# mp3.net
KiCad netlist of a schematic drawn in EAGLE
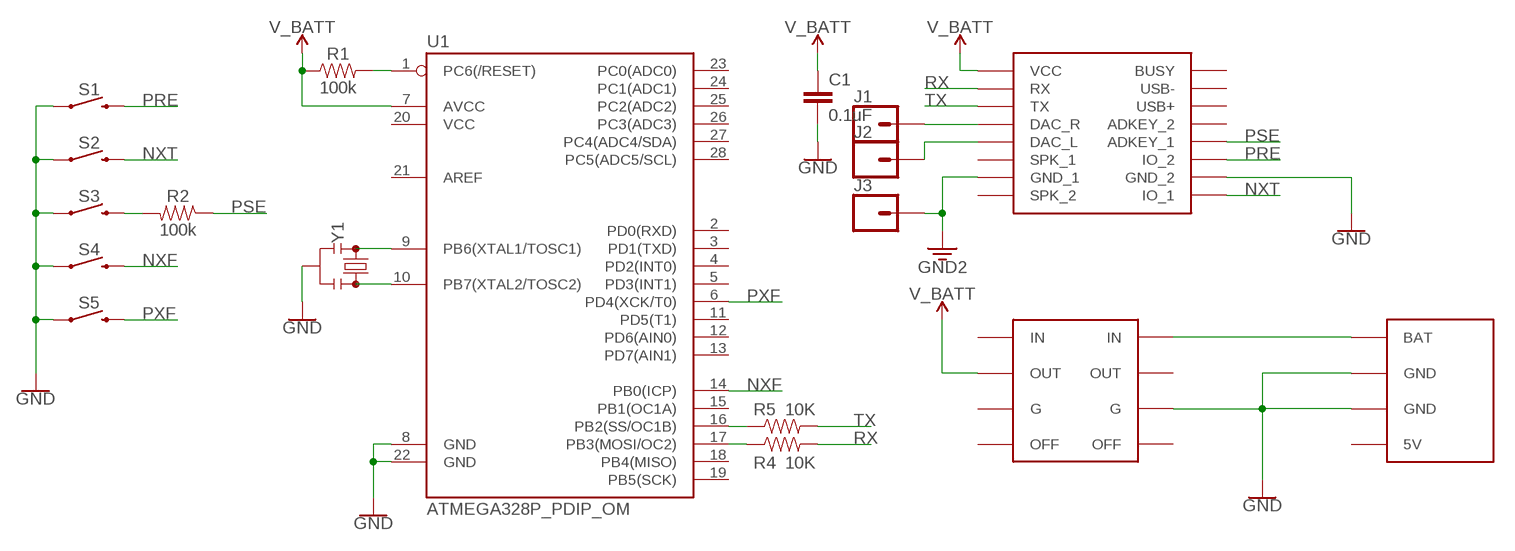
[diagram p0: schematic, sheet 1]

(export (version "E")
  (design (tool "Eeschema 10.0.6"))
  (components
    (comp (ref "C1")
      (value "0.1uF")
      (footprint "eagle-import:CAP-PTH-SMALL-KIT")
      (libsource (lib "eagle-import") (part "0.1UF-KIT-EZ-50V-20%"))
    )
    (comp (ref "J1")
      (value "CONN_01PTH_NO_SILK_KIT")
      (footprint "eagle-import:1X01NS_KIT")
      (libsource (lib "eagle-import") (part "CONN_01PTH_NO_SILK_KIT"))
    )
    (comp (ref "J2")
      (value "CONN_01PTH_NO_SILK_KIT")
      (footprint "eagle-import:1X01NS_KIT")
      (libsource (lib "eagle-import") (part "CONN_01PTH_NO_SILK_KIT"))
    )
    (comp (ref "J3")
      (value "CONN_01PTH_NO_SILK_KIT")
      (footprint "eagle-import:1X01NS_KIT")
      (libsource (lib "eagle-import") (part "CONN_01PTH_NO_SILK_KIT"))
    )
    (comp (ref "R1")
      (value "100k")
      (footprint "eagle-import:AXIAL-0.3")
      (libsource (lib "eagle-import") (part "100KOHM-HORIZ-1/4W-1%"))
    )
    (comp (ref "R2")
      (value "100k")
      (footprint "eagle-import:AXIAL-0.3")
      (libsource (lib "eagle-import") (part "100KOHM-HORIZ-1/4W-1%"))
    )
    (comp (ref "R4")
      (value "10K")
      (footprint "eagle-import:AXIAL-0.3")
      (libsource (lib "eagle-import") (part "100KOHM-HORIZ-1/4W-1%"))
    )
    (comp (ref "R5")
      (value "10K")
      (footprint "eagle-import:AXIAL-0.3")
      (libsource (lib "eagle-import") (part "100KOHM-HORIZ-1/4W-1%"))
    )
    (comp (ref "S1")
      (value "MOMENTARY-SWITCH-SPST-PTH-RIGHT-ANGLE")
      (footprint "eagle-import:TACTILE_SWITCH_PTH_RIGHT_ANGLE")
      (libsource (lib "eagle-import") (part "MOMENTARY-SWITCH-SPST-PTH-RIGHT-ANGLE"))
    )
    (comp (ref "S2")
      (value "MOMENTARY-SWITCH-SPST-PTH-RIGHT-ANGLE")
      (footprint "eagle-import:TACTILE_SWITCH_PTH_RIGHT_ANGLE")
      (libsource (lib "eagle-import") (part "MOMENTARY-SWITCH-SPST-PTH-RIGHT-ANGLE"))
    )
    (comp (ref "S3")
      (value "MOMENTARY-SWITCH-SPST-PTH-RIGHT-ANGLE")
      (footprint "eagle-import:TACTILE_SWITCH_PTH_RIGHT_ANGLE")
      (libsource (lib "eagle-import") (part "MOMENTARY-SWITCH-SPST-PTH-RIGHT-ANGLE"))
    )
    (comp (ref "S4")
      (value "MOMENTARY-SWITCH-SPST-PTH-RIGHT-ANGLE")
      (footprint "eagle-import:TACTILE_SWITCH_PTH_RIGHT_ANGLE")
      (libsource (lib "eagle-import") (part "MOMENTARY-SWITCH-SPST-PTH-RIGHT-ANGLE"))
    )
    (comp (ref "S5")
      (value "MOMENTARY-SWITCH-SPST-PTH-RIGHT-ANGLE")
      (footprint "eagle-import:TACTILE_SWITCH_PTH_RIGHT_ANGLE")
      (libsource (lib "eagle-import") (part "MOMENTARY-SWITCH-SPST-PTH-RIGHT-ANGLE"))
    )
    (comp (ref "U$1")
      (value "DFPLAYER")
      (footprint "eagle-import:DFPLAYER")
      (libsource (lib "eagle-import") (part "DFPLAYER"))
    )
    (comp (ref "U$2")
      (value "ADAFRUIT_SOFTPOWER")
      (footprint "eagle-import:ADAFRUIT_SOFTPOWER")
      (libsource (lib "eagle-import") (part "ADAFRUIT_SOFTPOWER"))
    )
    (comp (ref "U$3")
      (value "ADAFRUIT_CHARGER")
      (footprint "eagle-import:ADAFRUIT_CHARGER")
      (libsource (lib "eagle-import") (part "ADAFRUIT_CHARGER"))
    )
    (comp (ref "U1")
      (value "ATMEGA328P_PDIP_OM")
      (footprint "eagle-import:DIP28_OMILL")
      (libsource (lib "eagle-import") (part "ATMEGA328P_PDIP_OM"))
    )
    (comp (ref "Y1")
      (value "RESONATOROM")
      (footprint "eagle-import:RESONATOR-PTH-7.6X3.3-OM")
      (libsource (lib "eagle-import") (part "RESONATOROM"))
    )
  )
  (nets
    (net (code "1") (name "/NXF") (class "Default")
      (node (ref "S4") (pin "2") (pinfunction "2_2") (pintype "passive"))
      (node (ref "U1") (pin "14") (pinfunction "PB0(ICP)_14") (pintype "bidirectional"))
    )
    (net (code "2") (name "/NXT") (class "Default")
      (node (ref "S2") (pin "2") (pinfunction "2_2") (pintype "passive"))
      (node (ref "U$1") (pin "IO1") (pinfunction "IO_1_IO1") (pintype "bidirectional"))
    )
    (net (code "3") (name "/PRE") (class "Default")
      (node (ref "S1") (pin "2") (pinfunction "2_2") (pintype "passive"))
      (node (ref "U$1") (pin "IO2") (pinfunction "IO_2_IO2") (pintype "bidirectional"))
    )
    (net (code "4") (name "/PSE") (class "Default")
      (node (ref "R2") (pin "P$1") (pinfunction "1_P$1") (pintype "passive"))
      (node (ref "U$1") (pin "ADKEY1") (pinfunction "ADKEY_1_ADKEY1") (pintype "bidirectional"))
    )
    (net (code "5") (name "/PXF") (class "Default")
      (node (ref "S5") (pin "2") (pinfunction "2_2") (pintype "passive"))
      (node (ref "U1") (pin "6") (pinfunction "PD4(XCK/T0)_6") (pintype "bidirectional"))
    )
    (net (code "6") (name "/RX") (class "Default")
      (node (ref "R5") (pin "P$2") (pinfunction "2_P$2") (pintype "passive"))
      (node (ref "U$1") (pin "RX") (pinfunction "RX_RX") (pintype "bidirectional"))
    )
    (net (code "7") (name "/TX") (class "Default")
      (node (ref "R4") (pin "P$2") (pinfunction "2_P$2") (pintype "passive"))
      (node (ref "U$1") (pin "TX") (pinfunction "TX_TX") (pintype "bidirectional"))
    )
    (net (code "8") (name "GND") (class "Default")
      (node (ref "C1") (pin "2") (pinfunction "2_2") (pintype "passive"))
      (node (ref "S1") (pin "1") (pinfunction "1_1") (pintype "passive"))
      (node (ref "S2") (pin "1") (pinfunction "1_1") (pintype "passive"))
      (node (ref "S3") (pin "1") (pinfunction "1_1") (pintype "passive"))
      (node (ref "S4") (pin "1") (pinfunction "1_1") (pintype "passive"))
      (node (ref "S5") (pin "1") (pinfunction "1_1") (pintype "passive"))
      (node (ref "U$1") (pin "GND_2") (pinfunction "GND_2_GND_2") (pintype "bidirectional"))
      (node (ref "U$2") (pin "P$2") (pinfunction "G_P$2") (pintype "bidirectional"))
      (node (ref "U$3") (pin "P$2") (pinfunction "GND_P$2") (pintype "bidirectional"))
      (node (ref "U$3") (pin "P$3") (pinfunction "GND_P$3") (pintype "bidirectional"))
      (node (ref "U1") (pin "22") (pinfunction "GND_22") (pintype "bidirectional"))
      (node (ref "U1") (pin "8") (pinfunction "GND_8") (pintype "bidirectional"))
      (node (ref "Y1") (pin "2") (pinfunction "2_2") (pintype "passive"))
    )
    (net (code "9") (name "GND2") (class "Default")
      (node (ref "J3") (pin "1") (pinfunction "1_1") (pintype "passive"))
      (node (ref "U$1") (pin "GND_1") (pinfunction "GND_1_GND_1") (pintype "bidirectional"))
    )
    (net (code "10") (name "Net-(J1-Pad1)") (class "Default")
      (node (ref "J1") (pin "1") (pinfunction "1_1") (pintype "passive"))
      (node (ref "U$1") (pin "DAC_R") (pinfunction "DAC_R_DAC_R") (pintype "bidirectional"))
    )
    (net (code "11") (name "Net-(J2-Pad1)") (class "Default")
      (node (ref "J2") (pin "1") (pinfunction "1_1") (pintype "passive"))
      (node (ref "U$1") (pin "DAC_L") (pinfunction "DAC_L_DAC_L") (pintype "bidirectional"))
    )
    (net (code "12") (name "Net-(R1-2)") (class "Default")
      (node (ref "R1") (pin "P$2") (pinfunction "2_P$2") (pintype "passive"))
      (node (ref "U1") (pin "1") (pinfunction "PC6(/RESET)_1") (pintype "bidirectional"))
    )
    (net (code "13") (name "Net-(R2-2)") (class "Default")
      (node (ref "R2") (pin "P$2") (pinfunction "2_P$2") (pintype "passive"))
      (node (ref "S3") (pin "2") (pinfunction "2_2") (pintype "passive"))
    )
    (net (code "14") (name "Net-(R4-1)") (class "Default")
      (node (ref "R4") (pin "P$1") (pinfunction "1_P$1") (pintype "passive"))
      (node (ref "U1") (pin "16") (pinfunction "PB2(SS/OC1B)_16") (pintype "bidirectional"))
    )
    (net (code "15") (name "Net-(R5-1)") (class "Default")
      (node (ref "R5") (pin "P$1") (pinfunction "1_P$1") (pintype "passive"))
      (node (ref "U1") (pin "17") (pinfunction "PB3(MOSI/OC2)_17") (pintype "bidirectional"))
    )
    (net (code "16") (name "Net-(U$3-BAT)") (class "Default")
      (node (ref "U$2") (pin "P$4") (pinfunction "IN_P$4") (pintype "bidirectional"))
      (node (ref "U$3") (pin "P$1") (pinfunction "BAT_P$1") (pintype "bidirectional"))
    )
    (net (code "17") (name "Net-(U1-PB6(XTAL1{slash}TOSC1))") (class "Default")
      (node (ref "U1") (pin "9") (pinfunction "PB6(XTAL1/TOSC1)_9") (pintype "bidirectional"))
      (node (ref "Y1") (pin "1") (pinfunction "1_1") (pintype "passive"))
    )
    (net (code "18") (name "Net-(U1-PB7(XTAL2{slash}TOSC2))") (class "Default")
      (node (ref "U1") (pin "10") (pinfunction "PB7(XTAL2/TOSC2)_10") (pintype "bidirectional"))
      (node (ref "Y1") (pin "3") (pinfunction "3_3") (pintype "passive"))
    )
    (net (code "19") (name "V_BATT") (class "Default")
      (node (ref "C1") (pin "1") (pinfunction "1_1") (pintype "passive"))
      (node (ref "R1") (pin "P$1") (pinfunction "1_P$1") (pintype "passive"))
      (node (ref "U$1") (pin "VCC") (pinfunction "VCC_VCC") (pintype "bidirectional"))
      (node (ref "U$2") (pin "P$6") (pinfunction "OUT_P$6") (pintype "bidirectional"))
      (node (ref "U1") (pin "7") (pinfunction "AVCC_7") (pintype "bidirectional"))
    )
    (net (code "20") (name "unconnected-(U$1-ADKEY_2-PadADKEY2)") (class "Default")
      (node (ref "U$1") (pin "ADKEY2") (pinfunction "ADKEY_2_ADKEY2") (pintype "bidirectional"))
    )
    (net (code "21") (name "unconnected-(U$1-PadBUSY)") (class "Default")
      (node (ref "U$1") (pin "BUSY") (pinfunction "BUSY_BUSY") (pintype "bidirectional"))
    )
    (net (code "22") (name "unconnected-(U$1-PadUSB+)") (class "Default")
      (node (ref "U$1") (pin "USB+") (pinfunction "USB+_USB+") (pintype "bidirectional"))
    )
    (net (code "23") (name "unconnected-(U$1-PadUSB-)") (class "Default")
      (node (ref "U$1") (pin "USB-") (pinfunction "USB-_USB-") (pintype "bidirectional"))
    )
    (net (code "24") (name "unconnected-(U$1-SPK_1-PadSPK1)") (class "Default")
      (node (ref "U$1") (pin "SPK1") (pinfunction "SPK_1_SPK1") (pintype "bidirectional"))
    )
    (net (code "25") (name "unconnected-(U$1-SPK_2-PadSPK2)") (class "Default")
      (node (ref "U$1") (pin "SPK2") (pinfunction "SPK_2_SPK2") (pintype "bidirectional"))
    )
    (net (code "26") (name "unconnected-(U$2-G-PadP$7)") (class "Default")
      (node (ref "U$2") (pin "P$7") (pinfunction "G_P$7") (pintype "bidirectional"))
    )
    (net (code "27") (name "unconnected-(U$2-IN-PadP$5)") (class "Default")
      (node (ref "U$2") (pin "P$5") (pinfunction "IN_P$5") (pintype "bidirectional"))
    )
    (net (code "28") (name "unconnected-(U$2-OFF-PadP$1)") (class "Default")
      (node (ref "U$2") (pin "P$1") (pinfunction "OFF_P$1") (pintype "bidirectional"))
    )
    (net (code "29") (name "unconnected-(U$2-OFF-PadP$8)") (class "Default")
      (node (ref "U$2") (pin "P$8") (pinfunction "OFF_P$8") (pintype "bidirectional"))
    )
    (net (code "30") (name "unconnected-(U$2-OUT-PadP$3)") (class "Default")
      (node (ref "U$2") (pin "P$3") (pinfunction "OUT_P$3") (pintype "bidirectional"))
    )
    (net (code "31") (name "unconnected-(U$3-5V-PadP$4)") (class "Default")
      (node (ref "U$3") (pin "P$4") (pinfunction "5V_P$4") (pintype "bidirectional"))
    )
    (net (code "32") (name "unconnected-(U1-AREF-Pad21)") (class "Default")
      (node (ref "U1") (pin "21") (pinfunction "AREF_21") (pintype "bidirectional"))
    )
    (net (code "33") (name "unconnected-(U1-PB1(OC1A)-Pad15)") (class "Default")
      (node (ref "U1") (pin "15") (pinfunction "PB1(OC1A)_15") (pintype "bidirectional"))
    )
    (net (code "34") (name "unconnected-(U1-PB4(MISO)-Pad18)") (class "Default")
      (node (ref "U1") (pin "18") (pinfunction "PB4(MISO)_18") (pintype "bidirectional"))
    )
    (net (code "35") (name "unconnected-(U1-PB5(SCK)-Pad19)") (class "Default")
      (node (ref "U1") (pin "19") (pinfunction "PB5(SCK)_19") (pintype "bidirectional"))
    )
    (net (code "36") (name "unconnected-(U1-PC0(ADC0)-Pad23)") (class "Default")
      (node (ref "U1") (pin "23") (pinfunction "PC0(ADC0)_23") (pintype "bidirectional"))
    )
    (net (code "37") (name "unconnected-(U1-PC1(ADC1)-Pad24)") (class "Default")
      (node (ref "U1") (pin "24") (pinfunction "PC1(ADC1)_24") (pintype "bidirectional"))
    )
    (net (code "38") (name "unconnected-(U1-PC2(ADC2)-Pad25)") (class "Default")
      (node (ref "U1") (pin "25") (pinfunction "PC2(ADC2)_25") (pintype "bidirectional"))
    )
    (net (code "39") (name "unconnected-(U1-PC3(ADC3)-Pad26)") (class "Default")
      (node (ref "U1") (pin "26") (pinfunction "PC3(ADC3)_26") (pintype "bidirectional"))
    )
    (net (code "40") (name "unconnected-(U1-PC4(ADC4{slash}SDA)-Pad27)") (class "Default")
      (node (ref "U1") (pin "27") (pinfunction "PC4(ADC4/SDA)_27") (pintype "bidirectional"))
    )
    (net (code "41") (name "unconnected-(U1-PC5(ADC5{slash}SCL)-Pad28)") (class "Default")
      (node (ref "U1") (pin "28") (pinfunction "PC5(ADC5/SCL)_28") (pintype "bidirectional"))
    )
    (net (code "42") (name "unconnected-(U1-PD0(RXD)-Pad2)") (class "Default")
      (node (ref "U1") (pin "2") (pinfunction "PD0(RXD)_2") (pintype "bidirectional"))
    )
    (net (code "43") (name "unconnected-(U1-PD1(TXD)-Pad3)") (class "Default")
      (node (ref "U1") (pin "3") (pinfunction "PD1(TXD)_3") (pintype "bidirectional"))
    )
    (net (code "44") (name "unconnected-(U1-PD2(INT0)-Pad4)") (class "Default")
      (node (ref "U1") (pin "4") (pinfunction "PD2(INT0)_4") (pintype "bidirectional"))
    )
    (net (code "45") (name "unconnected-(U1-PD3(INT1)-Pad5)") (class "Default")
      (node (ref "U1") (pin "5") (pinfunction "PD3(INT1)_5") (pintype "bidirectional"))
    )
    (net (code "46") (name "unconnected-(U1-PD5(T1)-Pad11)") (class "Default")
      (node (ref "U1") (pin "11") (pinfunction "PD5(T1)_11") (pintype "bidirectional"))
    )
    (net (code "47") (name "unconnected-(U1-PD6(AIN0)-Pad12)") (class "Default")
      (node (ref "U1") (pin "12") (pinfunction "PD6(AIN0)_12") (pintype "bidirectional"))
    )
    (net (code "48") (name "unconnected-(U1-PD7(AIN1)-Pad13)") (class "Default")
      (node (ref "U1") (pin "13") (pinfunction "PD7(AIN1)_13") (pintype "bidirectional"))
    )
    (net (code "49") (name "unconnected-(U1-VCC-Pad20)") (class "Default")
      (node (ref "U1") (pin "20") (pinfunction "VCC_20") (pintype "bidirectional"))
    )
  )
)
